# SN74CBTLV3257DBQR.net
KiCad netlist of a schematic drawn in Altium Designer
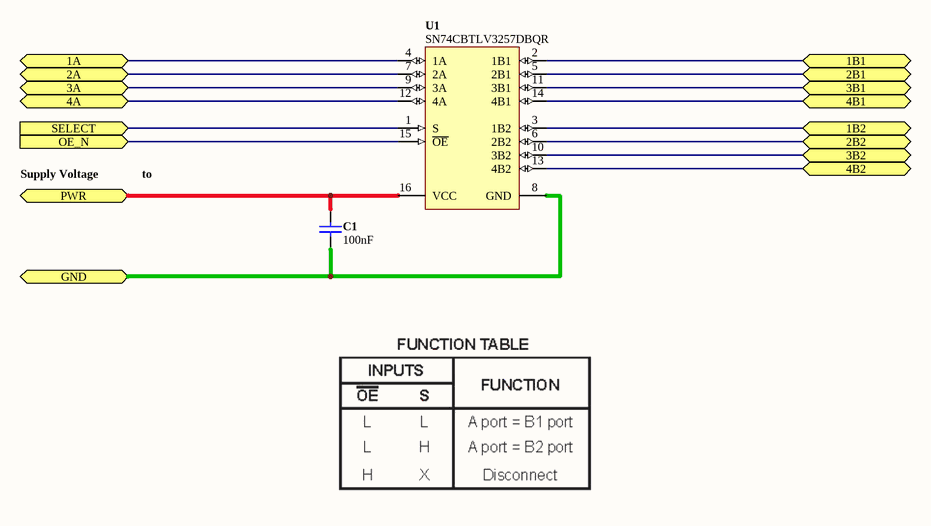
[diagram p0: SN74CBTLV3257DBQR.SchDoc]

(export (version "E")
  (design (tool "Eeschema 10.0.6"))
  (components
    (comp (ref "C1")
      (value "100nF")
      (footprint "CAPC0402(1005)60_N")
      (description "CAP 100nF 6.3V ±20% 0402 (1005 Metric) Thickness 0.6mm SMD")
      (fields (field (name "TOLERANCE") "±20%") (field (name "Comment") "CAP 100nF 6.3V 0402(1005)"))
      (libsource (lib "Altium Vault") (part "CMP-1034-02062-1"))
    )
    (comp (ref "U1")
      (value "SN74CBTLV3257DBQR")
      (footprint "SSOP-16_N")
      (description "IC QUAD 1:2 FET MUX/DEMUX 16SSOP")
      (libsource (lib "Altium Vault") (part "TI-SN74CBTLV3257_DBQR_16N"))
    )
  )
  (nets
    (net (code "1") (name "/1A") (class "Default")
      (node (ref "U1") (pin "4") (pinfunction "1A_4") (pintype "bidirectional"))
    )
    (net (code "2") (name "/1B1") (class "Default")
      (node (ref "U1") (pin "2") (pinfunction "1B1_2") (pintype "bidirectional"))
    )
    (net (code "3") (name "/1B2") (class "Default")
      (node (ref "U1") (pin "3") (pinfunction "1B2_3") (pintype "bidirectional"))
    )
    (net (code "4") (name "/2A") (class "Default")
      (node (ref "U1") (pin "7") (pinfunction "2A_7") (pintype "bidirectional"))
    )
    (net (code "5") (name "/2B1") (class "Default")
      (node (ref "U1") (pin "5") (pinfunction "2B1_5") (pintype "bidirectional"))
    )
    (net (code "6") (name "/2B2") (class "Default")
      (node (ref "U1") (pin "6") (pinfunction "2B2_6") (pintype "bidirectional"))
    )
    (net (code "7") (name "/3A") (class "Default")
      (node (ref "U1") (pin "9") (pinfunction "3A_9") (pintype "bidirectional"))
    )
    (net (code "8") (name "/3B1") (class "Default")
      (node (ref "U1") (pin "11") (pinfunction "3B1_11") (pintype "bidirectional"))
    )
    (net (code "9") (name "/3B2") (class "Default")
      (node (ref "U1") (pin "10") (pinfunction "3B2_10") (pintype "bidirectional"))
    )
    (net (code "10") (name "/4A") (class "Default")
      (node (ref "U1") (pin "12") (pinfunction "4A_12") (pintype "bidirectional"))
    )
    (net (code "11") (name "/4B1") (class "Default")
      (node (ref "U1") (pin "14") (pinfunction "4B1_14") (pintype "bidirectional"))
    )
    (net (code "12") (name "/4B2") (class "Default")
      (node (ref "U1") (pin "13") (pinfunction "4B2_13") (pintype "bidirectional"))
    )
    (net (code "13") (name "/GND") (class "Default")
      (node (ref "C1") (pin "1") (pinfunction "1_1") (pintype "passive"))
      (node (ref "U1") (pin "8") (pinfunction "GND_8") (pintype "power_in"))
    )
    (net (code "14") (name "/OE_N") (class "Default")
      (node (ref "U1") (pin "15") (pinfunction "~{OE}_15") (pintype "input"))
    )
    (net (code "15") (name "/PWR") (class "Default")
      (node (ref "C1") (pin "2") (pinfunction "2_2") (pintype "passive"))
      (node (ref "U1") (pin "16") (pinfunction "VCC_16") (pintype "power_in"))
    )
    (net (code "16") (name "/SELECT") (class "Default")
      (node (ref "U1") (pin "1") (pinfunction "S_1") (pintype "input"))
    )
  )
)
